# ALU_XOR.net
KiCad netlist of a schematic drawn in Altium Designer
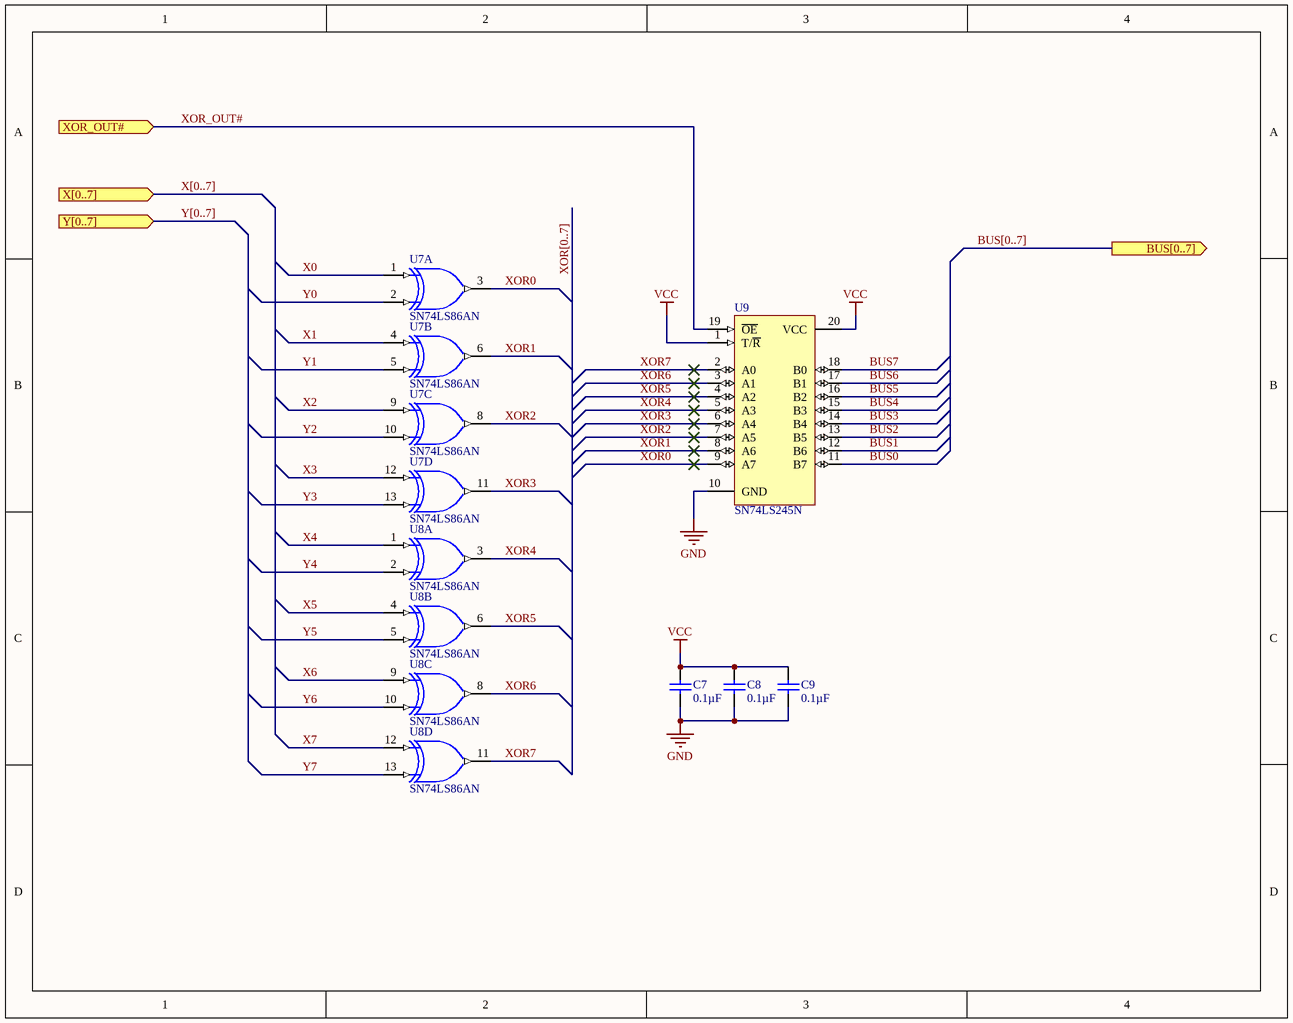
[diagram p0: ALU_XOR.SchDoc]

(export (version "E")
  (design (tool "Eeschema 10.0.6"))
  (components
    (comp (ref "C7")
      (value "K104K15X7RF5TL2")
      (footprint "VISH-K104K15X7RF5TL2")
      (description "Ceramic Capacitor, 100 nF, +/- 10%, 50 V, -55 to 125 degC, 2-Pin THD, RoHS, Tape and Reel")
      (fields
        (field (name "MANUFACTURER") "Vishay")
        (field (name "TOLERANCE") "±10%")
        (field (name "CAPACITANCE") "0.1µF")
      )
      (libsource (lib "Altium Content Vault") (part "CAP-NP-2"))
    )
    (comp (ref "C8")
      (value "K104K15X7RF5TL2")
      (footprint "VISH-K104K15X7RF5TL2")
      (description "Ceramic Capacitor, 100 nF, +/- 10%, 50 V, -55 to 125 degC, 2-Pin THD, RoHS, Tape and Reel")
      (fields
        (field (name "MANUFACTURER") "Vishay")
        (field (name "TOLERANCE") "±10%")
        (field (name "CAPACITANCE") "0.1µF")
      )
      (libsource (lib "Altium Content Vault") (part "CAP-NP-2"))
    )
    (comp (ref "C9")
      (value "K104K15X7RF5TL2")
      (footprint "VISH-K104K15X7RF5TL2")
      (description "Ceramic Capacitor, 100 nF, +/- 10%, 50 V, -55 to 125 degC, 2-Pin THD, RoHS, Tape and Reel")
      (fields
        (field (name "MANUFACTURER") "Vishay")
        (field (name "TOLERANCE") "±10%")
        (field (name "CAPACITANCE") "0.1µF")
      )
      (libsource (lib "Altium Content Vault") (part "CAP-NP-2"))
    )
    (comp (ref "U7")
      (value "SN74LS86AN")
      (footprint "N014")
      (description "Quadruple 2-Input Exclusive-OR Gate")
      (fields (field (name "PUBLISHER") "Altium Limited"))
      (libsource (lib "TI Logic Gate 2") (part "SN74LS86AN"))
    )
    (comp (ref "U8")
      (value "SN74LS86AN")
      (footprint "N014")
      (description "Quadruple 2-Input Exclusive-OR Gate")
      (fields (field (name "PUBLISHER") "Altium Limited"))
      (libsource (lib "TI Logic Gate 2") (part "SN74LS86AN"))
    )
    (comp (ref "U9")
      (value "SN74LS245N")
      (footprint "N020")
      (description "Octal Bus Transceiver with 3-State Outputs")
      (fields (field (name "PUBLISHER") "Altium Limited"))
      (libsource (lib "TI Interface 8-Bit Line Transceiver") (part "SN74LS245N"))
    )
  )
  (nets
    (net (code "1") (name "/BUS0") (class "Default")
      (node (ref "U9") (pin "11") (pinfunction "B7_11") (pintype "bidirectional"))
    )
    (net (code "2") (name "/BUS1") (class "Default")
      (node (ref "U9") (pin "12") (pinfunction "B6_12") (pintype "bidirectional"))
    )
    (net (code "3") (name "/BUS2") (class "Default")
      (node (ref "U9") (pin "13") (pinfunction "B5_13") (pintype "bidirectional"))
    )
    (net (code "4") (name "/BUS3") (class "Default")
      (node (ref "U9") (pin "14") (pinfunction "B4_14") (pintype "bidirectional"))
    )
    (net (code "5") (name "/BUS4") (class "Default")
      (node (ref "U9") (pin "15") (pinfunction "B3_15") (pintype "bidirectional"))
    )
    (net (code "6") (name "/BUS5") (class "Default")
      (node (ref "U9") (pin "16") (pinfunction "B2_16") (pintype "bidirectional"))
    )
    (net (code "7") (name "/BUS6") (class "Default")
      (node (ref "U9") (pin "17") (pinfunction "B1_17") (pintype "bidirectional"))
    )
    (net (code "8") (name "/BUS7") (class "Default")
      (node (ref "U9") (pin "18") (pinfunction "B0_18") (pintype "bidirectional"))
    )
    (net (code "10") (name "/X0") (class "Default")
      (node (ref "U7") (pin "1") (pinfunction "A_1") (pintype "input"))
    )
    (net (code "11") (name "/X1") (class "Default")
      (node (ref "U7") (pin "4") (pinfunction "A_4") (pintype "input"))
    )
    (net (code "12") (name "/X2") (class "Default")
      (node (ref "U7") (pin "9") (pinfunction "A_9") (pintype "input"))
    )
    (net (code "13") (name "/X3") (class "Default")
      (node (ref "U7") (pin "12") (pinfunction "A_12") (pintype "input"))
    )
    (net (code "14") (name "/X4") (class "Default")
      (node (ref "U8") (pin "1") (pinfunction "A_1") (pintype "input"))
    )
    (net (code "15") (name "/X5") (class "Default")
      (node (ref "U8") (pin "4") (pinfunction "A_4") (pintype "input"))
    )
    (net (code "16") (name "/X6") (class "Default")
      (node (ref "U8") (pin "9") (pinfunction "A_9") (pintype "input"))
    )
    (net (code "17") (name "/X7") (class "Default")
      (node (ref "U8") (pin "12") (pinfunction "A_12") (pintype "input"))
    )
    (net (code "18") (name "/XOR0") (class "Default")
      (node (ref "U7") (pin "3") (pinfunction "Y_3") (pintype "output"))
      (node (ref "U9") (pin "9") (pinfunction "A7_9") (pintype "bidirectional"))
    )
    (net (code "19") (name "/XOR1") (class "Default")
      (node (ref "U7") (pin "6") (pinfunction "Y_6") (pintype "output"))
      (node (ref "U9") (pin "8") (pinfunction "A6_8") (pintype "bidirectional"))
    )
    (net (code "20") (name "/XOR2") (class "Default")
      (node (ref "U7") (pin "8") (pinfunction "Y_8") (pintype "output"))
      (node (ref "U9") (pin "7") (pinfunction "A5_7") (pintype "bidirectional"))
    )
    (net (code "21") (name "/XOR3") (class "Default")
      (node (ref "U7") (pin "11") (pinfunction "Y_11") (pintype "output"))
      (node (ref "U9") (pin "6") (pinfunction "A4_6") (pintype "bidirectional"))
    )
    (net (code "22") (name "/XOR4") (class "Default")
      (node (ref "U8") (pin "3") (pinfunction "Y_3") (pintype "output"))
      (node (ref "U9") (pin "5") (pinfunction "A3_5") (pintype "bidirectional"))
    )
    (net (code "23") (name "/XOR5") (class "Default")
      (node (ref "U8") (pin "6") (pinfunction "Y_6") (pintype "output"))
      (node (ref "U9") (pin "4") (pinfunction "A2_4") (pintype "bidirectional"))
    )
    (net (code "24") (name "/XOR6") (class "Default")
      (node (ref "U8") (pin "8") (pinfunction "Y_8") (pintype "output"))
      (node (ref "U9") (pin "3") (pinfunction "A1_3") (pintype "bidirectional"))
    )
    (net (code "25") (name "/XOR7") (class "Default")
      (node (ref "U8") (pin "11") (pinfunction "Y_11") (pintype "output"))
      (node (ref "U9") (pin "2") (pinfunction "A0_2") (pintype "bidirectional"))
    )
    (net (code "27") (name "/XOR_OUT#") (class "Default")
      (node (ref "U9") (pin "19") (pinfunction "~{OE}_19") (pintype "input"))
    )
    (net (code "29") (name "/Y0") (class "Default")
      (node (ref "U7") (pin "2") (pinfunction "B_2") (pintype "input"))
    )
    (net (code "30") (name "/Y1") (class "Default")
      (node (ref "U7") (pin "5") (pinfunction "B_5") (pintype "input"))
    )
    (net (code "31") (name "/Y2") (class "Default")
      (node (ref "U7") (pin "10") (pinfunction "B_10") (pintype "input"))
    )
    (net (code "32") (name "/Y3") (class "Default")
      (node (ref "U7") (pin "13") (pinfunction "B_13") (pintype "input"))
    )
    (net (code "33") (name "/Y4") (class "Default")
      (node (ref "U8") (pin "2") (pinfunction "B_2") (pintype "input"))
    )
    (net (code "34") (name "/Y5") (class "Default")
      (node (ref "U8") (pin "5") (pinfunction "B_5") (pintype "input"))
    )
    (net (code "35") (name "/Y6") (class "Default")
      (node (ref "U8") (pin "10") (pinfunction "B_10") (pintype "input"))
    )
    (net (code "36") (name "/Y7") (class "Default")
      (node (ref "U8") (pin "13") (pinfunction "B_13") (pintype "input"))
    )
    (net (code "38") (name "GND") (class "Default")
      (node (ref "C7") (pin "2") (pinfunction "2_2") (pintype "passive"))
      (node (ref "C8") (pin "2") (pinfunction "2_2") (pintype "passive"))
      (node (ref "C9") (pin "2") (pinfunction "2_2") (pintype "passive"))
      (node (ref "U7") (pin "7") (pinfunction "GND_7") (pintype "power_in"))
      (node (ref "U8") (pin "7") (pinfunction "GND_7") (pintype "power_in"))
      (node (ref "U9") (pin "10") (pinfunction "GND_10") (pintype "power_in"))
    )
    (net (code "39") (name "VCC") (class "Default")
      (node (ref "C7") (pin "1") (pinfunction "1_1") (pintype "passive"))
      (node (ref "C8") (pin "1") (pinfunction "1_1") (pintype "passive"))
      (node (ref "C9") (pin "1") (pinfunction "1_1") (pintype "passive"))
      (node (ref "U7") (pin "14") (pinfunction "VCC_14") (pintype "power_in"))
      (node (ref "U8") (pin "14") (pinfunction "VCC_14") (pintype "power_in"))
      (node (ref "U9") (pin "1") (pinfunction "T/~{R}_1") (pintype "input"))
      (node (ref "U9") (pin "20") (pinfunction "VCC_20") (pintype "power_in"))
    )
  )
)
